# CCS811_Rev_B.net
KiCad netlist of a schematic drawn in EAGLE
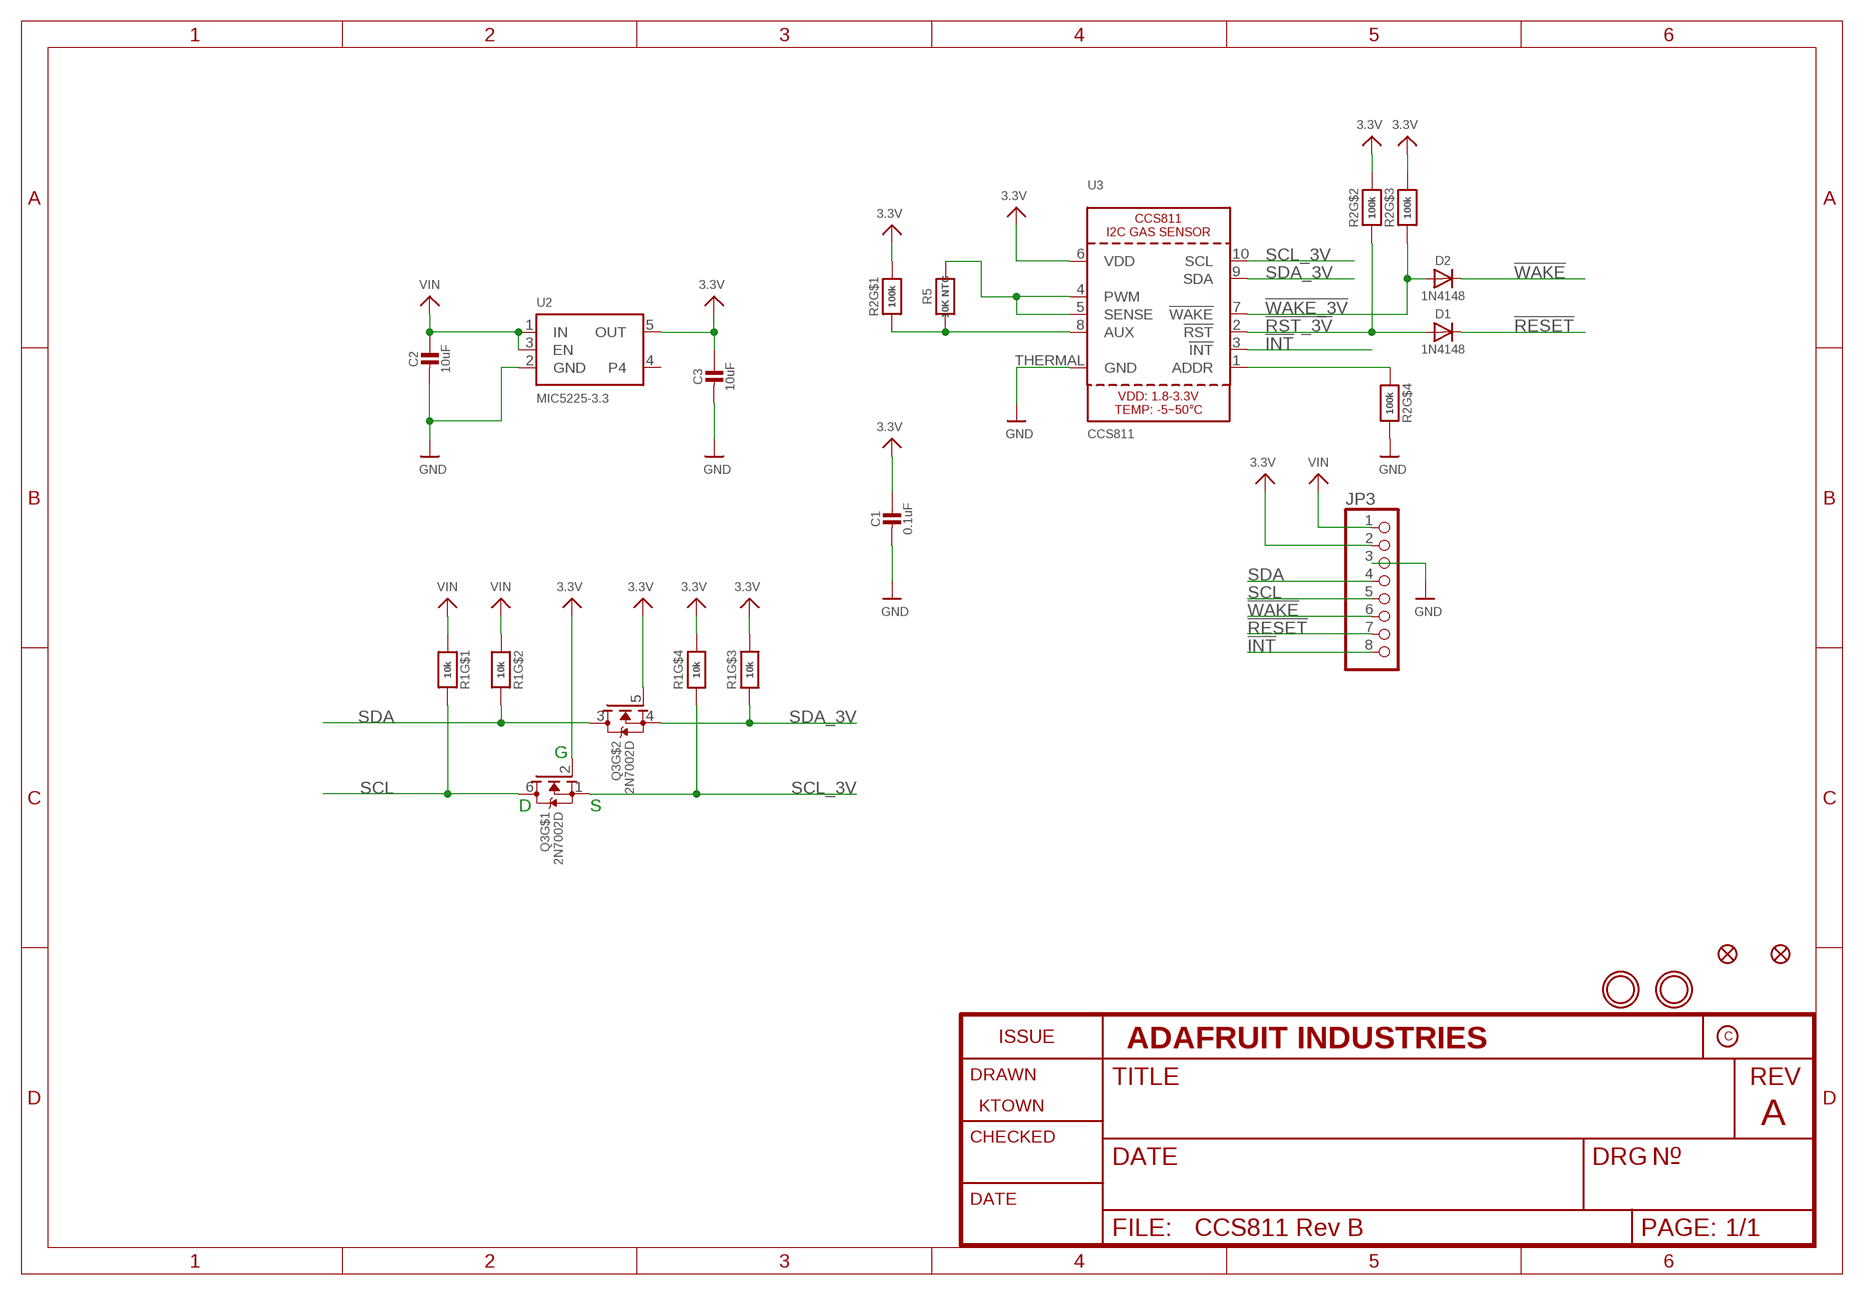
[diagram p0: schematic, sheet 1]

(export (version "E")
  (design (tool "Eeschema 10.0.6"))
  (components
    (comp (ref "C1")
      (value "0.1uF")
      (footprint "eagle-import:0603-NO")
      (libsource (lib "eagle-import") (part "CAP_CERAMIC0603_NO"))
    )
    (comp (ref "C2")
      (value "10uF")
      (footprint "eagle-import:0805-NO")
      (libsource (lib "eagle-import") (part "CAP_CERAMIC0805-NOOUTLINE"))
    )
    (comp (ref "C3")
      (value "10uF")
      (footprint "eagle-import:0805-NO")
      (libsource (lib "eagle-import") (part "CAP_CERAMIC0805-NOOUTLINE"))
    )
    (comp (ref "D1")
      (value "1N4148")
      (footprint "eagle-import:SOD-323")
      (libsource (lib "eagle-import") (part "DIODESOD-323"))
    )
    (comp (ref "D2")
      (value "1N4148")
      (footprint "eagle-import:SOD-323")
      (libsource (lib "eagle-import") (part "DIODESOD-323"))
    )
    (comp (ref "FID1")
      (value "FIDUCIAL_1MM")
      (footprint "eagle-import:FIDUCIAL_1MM")
      (libsource (lib "eagle-import") (part "FIDUCIAL_1MM"))
    )
    (comp (ref "FID2")
      (value "FIDUCIAL_1MM")
      (footprint "eagle-import:FIDUCIAL_1MM")
      (libsource (lib "eagle-import") (part "FIDUCIAL_1MM"))
    )
    (comp (ref "JP3")
      (value "HEADER-1X870MIL")
      (footprint "eagle-import:1X08_ROUND_70")
      (libsource (lib "eagle-import") (part "HEADER-1X870MIL"))
    )
    (comp (ref "Q3")
      (value "2N7002D")
      (footprint "eagle-import:SOT363")
      (libsource (lib "eagle-import") (part "MOSFET-N_DUAL"))
    )
    (comp (ref "R1")
      (value "10k")
      (footprint "eagle-import:RESPACK_4X0603")
      (libsource (lib "eagle-import") (part "RESISTOR_4PACK"))
    )
    (comp (ref "R2")
      (value "100k")
      (footprint "eagle-import:RESPACK_4X0603")
      (libsource (lib "eagle-import") (part "RESISTOR_4PACK"))
    )
    (comp (ref "R5")
      (value "10K NTC")
      (footprint "eagle-import:_0402")
      (libsource (lib "eagle-import") (part "RESISTOR_0402"))
    )
    (comp (ref "U$3")
      (value "MOUNTINGHOLE2.5")
      (footprint "eagle-import:MOUNTINGHOLE_2.5_PLATED")
      (libsource (lib "eagle-import") (part "MOUNTINGHOLE2.5"))
    )
    (comp (ref "U$4")
      (value "MOUNTINGHOLE2.5")
      (footprint "eagle-import:MOUNTINGHOLE_2.5_PLATED")
      (libsource (lib "eagle-import") (part "MOUNTINGHOLE2.5"))
    )
    (comp (ref "U2")
      (value "MIC5225-3.3")
      (footprint "eagle-import:SOT23-5")
      (libsource (lib "eagle-import") (part "VREG_SOT23-5"))
    )
    (comp (ref "U3")
      (value "CCS811")
      (footprint "eagle-import:CCS811")
      (libsource (lib "eagle-import") (part "CCS811"))
    )
  )
  (nets
    (net (code "1") (name "/SCL") (class "Default")
      (node (ref "JP3") (pin "5") (pinfunction "5_5") (pintype "passive"))
      (node (ref "Q3") (pin "6") (pinfunction "D_6") (pintype "bidirectional"))
      (node (ref "R1") (pin "8") (pinfunction "2_8") (pintype "passive"))
    )
    (net (code "2") (name "/SCL_3V") (class "Default")
      (node (ref "Q3") (pin "1") (pinfunction "S_1") (pintype "bidirectional"))
      (node (ref "R1") (pin "5") (pinfunction "2_5") (pintype "passive"))
      (node (ref "U3") (pin "10") (pinfunction "SCL_10") (pintype "bidirectional"))
    )
    (net (code "3") (name "/SDA") (class "Default")
      (node (ref "JP3") (pin "4") (pinfunction "4_4") (pintype "passive"))
      (node (ref "Q3") (pin "3") (pinfunction "D_3") (pintype "bidirectional"))
      (node (ref "R1") (pin "7") (pinfunction "2_7") (pintype "passive"))
    )
    (net (code "4") (name "/SDA_3V") (class "Default")
      (node (ref "Q3") (pin "4") (pinfunction "S_4") (pintype "bidirectional"))
      (node (ref "R1") (pin "6") (pinfunction "2_6") (pintype "passive"))
      (node (ref "U3") (pin "9") (pinfunction "SDA_9") (pintype "bidirectional"))
    )
    (net (code "5") (name "/~{INT}") (class "Default")
      (node (ref "JP3") (pin "8") (pinfunction "8_8") (pintype "passive"))
      (node (ref "U3") (pin "3") (pinfunction "~{INT}_3") (pintype "output"))
    )
    (net (code "6") (name "/~{RESET}") (class "Default")
      (node (ref "D1") (pin "C") (pinfunction "C_C") (pintype "passive"))
      (node (ref "JP3") (pin "7") (pinfunction "7_7") (pintype "passive"))
    )
    (net (code "7") (name "/~{RST_3V}") (class "Default")
      (node (ref "D1") (pin "A") (pinfunction "A_A") (pintype "passive"))
      (node (ref "R2") (pin "2") (pinfunction "1_2") (pintype "passive"))
      (node (ref "U3") (pin "2") (pinfunction "~{RST}_2") (pintype "input"))
    )
    (net (code "8") (name "/~{WAKE_3V}") (class "Default")
      (node (ref "D2") (pin "A") (pinfunction "A_A") (pintype "passive"))
      (node (ref "R2") (pin "3") (pinfunction "1_3") (pintype "passive"))
      (node (ref "U3") (pin "7") (pinfunction "~{WAKE}_7") (pintype "input"))
    )
    (net (code "9") (name "/~{WAKE}") (class "Default")
      (node (ref "D2") (pin "C") (pinfunction "C_C") (pintype "passive"))
      (node (ref "JP3") (pin "6") (pinfunction "6_6") (pintype "passive"))
    )
    (net (code "10") (name "3.3V") (class "Default")
      (node (ref "C1") (pin "1") (pinfunction "1_1") (pintype "passive"))
      (node (ref "C3") (pin "1") (pinfunction "1_1") (pintype "passive"))
      (node (ref "JP3") (pin "2") (pinfunction "2_2") (pintype "passive"))
      (node (ref "Q3") (pin "2") (pinfunction "G_2") (pintype "bidirectional"))
      (node (ref "Q3") (pin "5") (pinfunction "G_5") (pintype "bidirectional"))
      (node (ref "R1") (pin "3") (pinfunction "1_3") (pintype "passive"))
      (node (ref "R1") (pin "4") (pinfunction "1_4") (pintype "passive"))
      (node (ref "R2") (pin "6") (pinfunction "2_6") (pintype "passive"))
      (node (ref "R2") (pin "7") (pinfunction "2_7") (pintype "passive"))
      (node (ref "R2") (pin "8") (pinfunction "2_8") (pintype "passive"))
      (node (ref "U2") (pin "5") (pinfunction "OUT_5") (pintype "power_in"))
      (node (ref "U3") (pin "6") (pinfunction "VDD_6") (pintype "power_in"))
    )
    (net (code "11") (name "GND") (class "Default")
      (node (ref "C1") (pin "2") (pinfunction "2_2") (pintype "passive"))
      (node (ref "C2") (pin "2") (pinfunction "2_2") (pintype "passive"))
      (node (ref "C3") (pin "2") (pinfunction "2_2") (pintype "passive"))
      (node (ref "JP3") (pin "3") (pinfunction "3_3") (pintype "passive"))
      (node (ref "R2") (pin "5") (pinfunction "2_5") (pintype "passive"))
      (node (ref "U2") (pin "2") (pinfunction "GND_2") (pintype "power_in"))
      (node (ref "U3") (pin "THERMAL") (pinfunction "GND_THERMAL") (pintype "power_in"))
    )
    (net (code "12") (name "Net-(R2D-1)") (class "Default")
      (node (ref "R2") (pin "4") (pinfunction "1_4") (pintype "passive"))
      (node (ref "U3") (pin "1") (pinfunction "ADDR_1") (pintype "input"))
    )
    (net (code "13") (name "Net-(U3-AUX)") (class "Default")
      (node (ref "R2") (pin "1") (pinfunction "1_1") (pintype "passive"))
      (node (ref "R5") (pin "1") (pinfunction "1_1") (pintype "passive"))
      (node (ref "U3") (pin "8") (pinfunction "AUX_8") (pintype "passive"))
    )
    (net (code "14") (name "Net-(U3-PWM)") (class "Default")
      (node (ref "R5") (pin "2") (pinfunction "2_2") (pintype "passive"))
      (node (ref "U3") (pin "4") (pinfunction "PWM_4") (pintype "output"))
      (node (ref "U3") (pin "5") (pinfunction "SENSE_5") (pintype "input"))
    )
    (net (code "15") (name "VIN") (class "Default")
      (node (ref "C2") (pin "1") (pinfunction "1_1") (pintype "passive"))
      (node (ref "JP3") (pin "1") (pinfunction "1_1") (pintype "passive"))
      (node (ref "R1") (pin "1") (pinfunction "1_1") (pintype "passive"))
      (node (ref "R1") (pin "2") (pinfunction "1_2") (pintype "passive"))
      (node (ref "U2") (pin "1") (pinfunction "IN_1") (pintype "power_in"))
      (node (ref "U2") (pin "3") (pinfunction "EN_3") (pintype "input"))
    )
    (net (code "16") (name "unconnected-(U2-P4-Pad4)") (class "Default")
      (node (ref "U2") (pin "4") (pinfunction "P4_4") (pintype "bidirectional"))
    )
  )
)
